# 3_waffling60-MX_mcu.net
KiCad netlist of a schematic drawn in Altium Designer
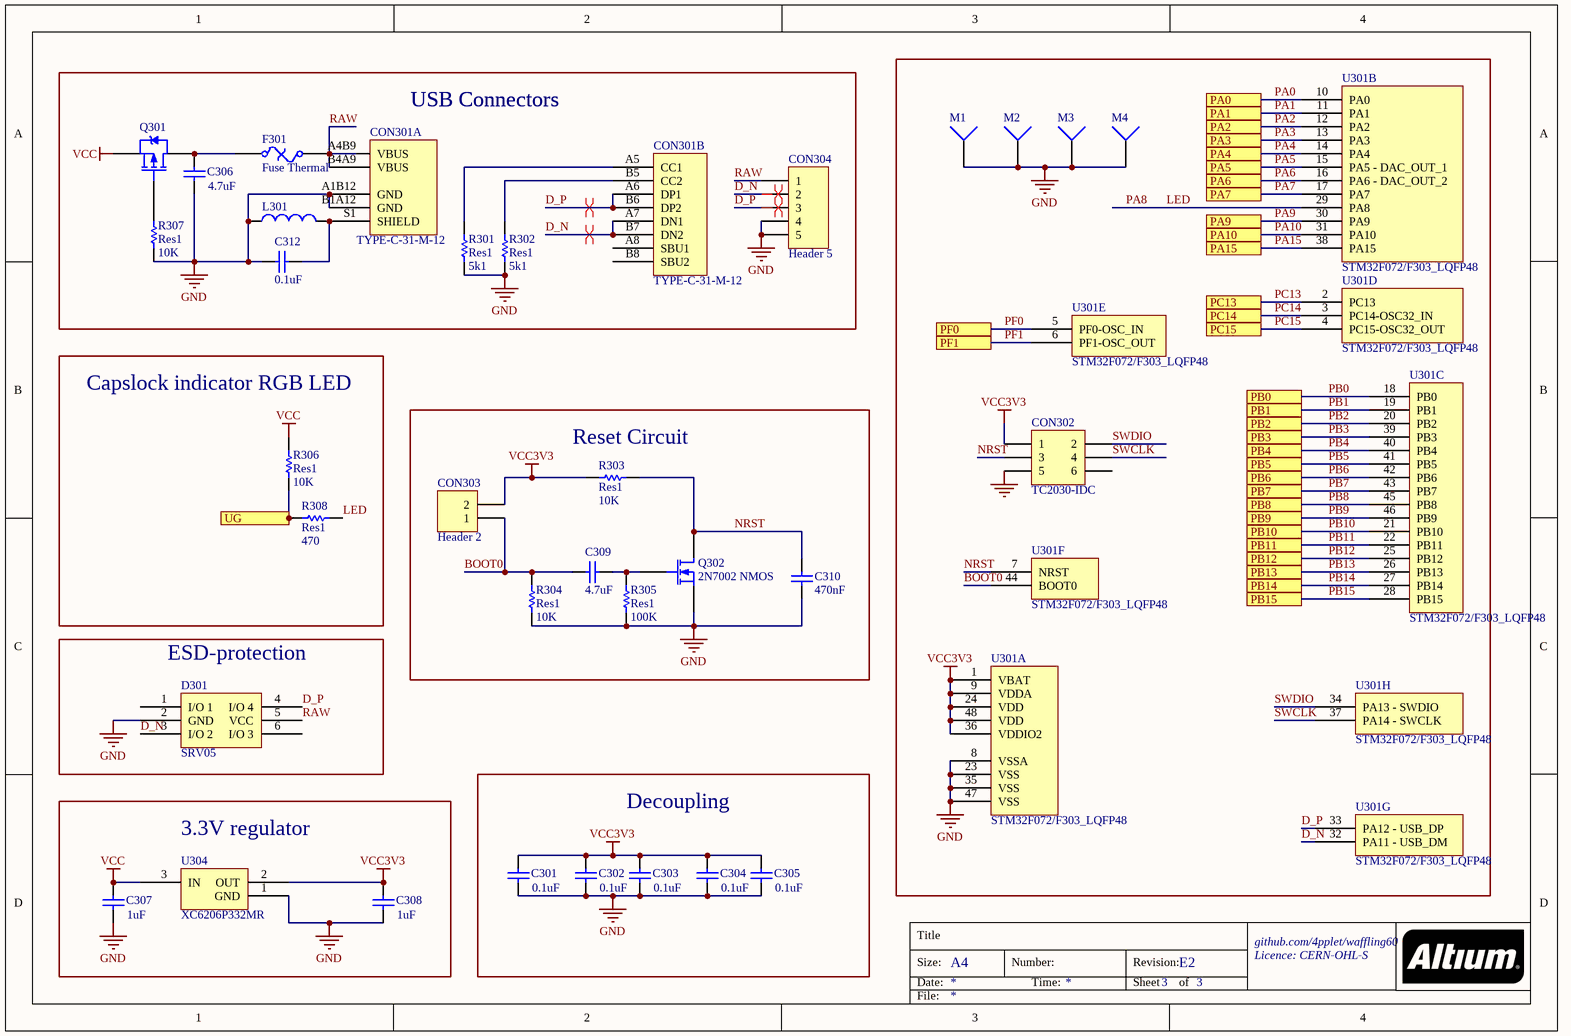
[diagram p0: 3_waffling60-MX_mcu.SchDoc]

(export (version "E")
  (design (tool "Eeschema 10.0.6"))
  (components
    (comp (ref "C301")
      (value "0.1uF")
      (footprint "C0603[1608]")
      (description "Capacitor")
      (fields (field (name "LCSC PART #") "C14663") (field (name "MRF.PART") "CC0603KRX7R9BB104"))
      (libsource (lib "Miscellaneous Devices") (part "Cap"))
    )
    (comp (ref "C302")
      (value "0.1uF")
      (footprint "C0603[1608]")
      (description "Capacitor")
      (fields (field (name "LCSC PART #") "C14663") (field (name "MRF.PART") "CC0603KRX7R9BB104"))
      (libsource (lib "Miscellaneous Devices") (part "Cap"))
    )
    (comp (ref "C303")
      (value "0.1uF")
      (footprint "C0603[1608]")
      (description "Capacitor")
      (fields (field (name "LCSC PART #") "C14663") (field (name "MRF.PART") "CC0603KRX7R9BB104"))
      (libsource (lib "Miscellaneous Devices") (part "Cap"))
    )
    (comp (ref "C304")
      (value "0.1uF")
      (footprint "C0603[1608]")
      (description "Capacitor")
      (fields (field (name "LCSC PART #") "C14663") (field (name "MRF.PART") "CC0603KRX7R9BB104"))
      (libsource (lib "Miscellaneous Devices") (part "Cap"))
    )
    (comp (ref "C305")
      (value "0.1uF")
      (footprint "C0603[1608]")
      (description "Capacitor")
      (fields (field (name "LCSC PART #") "C14663") (field (name "MRF.PART") "CC0603KRX7R9BB104"))
      (libsource (lib "Miscellaneous Devices") (part "Cap"))
    )
    (comp (ref "C306")
      (value "4.7uF")
      (footprint "C0603[1608]")
      (description "Capacitor")
      (fields (field (name "LCSC PART #") "C19666") (field (name "MRF.PART") "CL10A475KO8NNNC"))
      (libsource (lib "Miscellaneous Devices") (part "Cap"))
    )
    (comp (ref "C307")
      (value "1uF")
      (footprint "C0603[1608]")
      (description "Capacitor")
      (fields (field (name "LCSC PART #") "C15849") (field (name "MRF.PART") "CL10A105KB8NNNC"))
      (libsource (lib "Miscellaneous Devices") (part "Cap"))
    )
    (comp (ref "C308")
      (value "1uF")
      (footprint "C0603[1608]")
      (description "Capacitor")
      (fields (field (name "LCSC PART #") "C15849") (field (name "MRF.PART") "CL10A105KB8NNNC"))
      (libsource (lib "Miscellaneous Devices") (part "Cap"))
    )
    (comp (ref "C309")
      (value "4.7uF")
      (footprint "C0603[1608]")
      (description "Capacitor")
      (fields (field (name "LCSC PART #") "C19666") (field (name "MRF.PART") "CL10A475KO8NNNC"))
      (libsource (lib "Miscellaneous Devices") (part "Cap"))
    )
    (comp (ref "C310")
      (value "470nF")
      (footprint "C0603[1608]")
      (description "Capacitor")
      (fields (field (name "LCSC PART #") "C1623") (field (name "MRF.PART") "CL10B474KA8NNNC"))
      (libsource (lib "Miscellaneous Devices") (part "Cap"))
    )
    (comp (ref "C312")
      (value "0.1uF")
      (footprint "C0603[1608]")
      (description "Capacitor")
      (fields (field (name "LCSC PART #") "C14663") (field (name "MRF.PART") "CC0603KRX7R9BB104"))
      (libsource (lib "Miscellaneous Devices") (part "Cap"))
    )
    (comp (ref "CON301")
      (value "TYPE-C-31-M-12")
      (footprint "TYPE-C-31-M-12")
      (fields (field (name "LCSC PART #") "C165948"))
      (libsource (lib "Schlib1") (part "TYPE-C-31-M-12"))
    )
    (comp (ref "CON302")
      (value "TC2030-IDC")
      (footprint "TC2030-IDC-NL")
      (description "Header, 3-Pin, Dual row")
      (libsource (lib "Miscellaneous Connectors") (part "Header 3X2"))
    )
    (comp (ref "CON303")
      (value "Header 2")
      (footprint "HDR1X2")
      (description "Header, 2-Pin")
      (libsource (lib "Miscellaneous Connectors") (part "Header 2"))
    )
    (comp (ref "CON304")
      (value "Header 5")
      (footprint "UDB_COMBO_JST_MOLEX")
      (description "JST for USB daughter board")
      (fields (field (name "LCSC PART #") "C145956"))
      (libsource (lib "Miscellaneous Connectors") (part "Header 5"))
    )
    (comp (ref "D301")
      (value "SRV05")
      (footprint "SOT-23-6")
      (fields (field (name "LCSC PART #") "C85364") (field (name "MRF.PART") "SRV05-4-P-T7"))
      (libsource (lib "Keebs") (part "SRV05"))
    )
    (comp (ref "F301")
      (value "Fuse Thermal")
      (footprint "C1206[3216]")
      (description "Thermal Fuse")
      (fields (field (name "LCSC PART #") "C135338") (field (name "MRF.PART") "ASMD1206-050"))
      (libsource (lib "Miscellaneous Devices") (part "Fuse Thermal"))
    )
    (comp (ref "L301")
      (value "Inductor")
      (footprint "L0805")
      (fields (field (name "LCSC PART #") "C1015") (field (name "MRF.PART") "GZ2012D101TF"))
      (libsource (lib "Simulation Generic Components") (part "Inductor"))
    )
    (comp (ref "M1")
      (value "Socket")
      (footprint "mounting_hole")
      (libsource (lib "Miscellaneous Connectors") (part "Socket"))
    )
    (comp (ref "M2")
      (value "Socket")
      (footprint "mounting_hole")
      (libsource (lib "Miscellaneous Connectors") (part "Socket"))
    )
    (comp (ref "M3")
      (value "Socket")
      (footprint "mounting_hole")
      (libsource (lib "Miscellaneous Connectors") (part "Socket"))
    )
    (comp (ref "M4")
      (value "Socket")
      (footprint "mounting_hole")
      (libsource (lib "Miscellaneous Connectors") (part "Socket"))
    )
    (comp (ref "Q301")
      (value "PMOS-2")
      (footprint "SOT-23-3")
      (description "P-Channel Power MOSFET")
      (fields (field (name "LCSC PART #") "C10487") (field (name "MRF.PART") "SI2301CDS-T1-GE3"))
      (libsource (lib "Miscellaneous Devices") (part "PMOS-2"))
    )
    (comp (ref "Q302")
      (value "2N7002 NMOS")
      (footprint "SOT-23-3")
      (description "N-Channel MOSFET")
      (fields (field (name "LCSC PART #") "C8545") (field (name "MRF.PART") "2N7002"))
      (libsource (lib "Miscellaneous Devices") (part "MOSFET-N"))
    )
    (comp (ref "R301")
      (value "Res1")
      (footprint "R0603[1608]")
      (description "Resistor")
      (fields
        (field (name "ALTIUM_VALUE") "5k1")
        (field (name "LCSC PART #") "C23186")
        (field (name "MRF.PART") "0603WAF5101T5E")
      )
      (libsource (lib "Miscellaneous Devices") (part "Res1"))
    )
    (comp (ref "R302")
      (value "Res1")
      (footprint "R0603[1608]")
      (description "Resistor")
      (fields
        (field (name "ALTIUM_VALUE") "5k1")
        (field (name "LCSC PART #") "C23186")
        (field (name "MRF.PART") "0603WAF5101T5E")
      )
      (libsource (lib "Miscellaneous Devices") (part "Res1"))
    )
    (comp (ref "R303")
      (value "Res1")
      (footprint "R0603[1608]")
      (description "Resistor")
      (fields
        (field (name "ALTIUM_VALUE") "10K")
        (field (name "LCSC PART #") "C25804")
        (field (name "MRF.PART") "0603WAF1002T5E")
      )
      (libsource (lib "Miscellaneous Devices") (part "Res1"))
    )
    (comp (ref "R304")
      (value "Res1")
      (footprint "R0603[1608]")
      (description "Resistor")
      (fields
        (field (name "ALTIUM_VALUE") "10K")
        (field (name "LCSC PART #") "C25804")
        (field (name "MRF.PART") "0603WAF1002T5E")
      )
      (libsource (lib "Miscellaneous Devices") (part "Res1"))
    )
    (comp (ref "R305")
      (value "Res1")
      (footprint "R0603[1608]")
      (description "Resistor")
      (fields
        (field (name "ALTIUM_VALUE") "100K")
        (field (name "LCSC PART #") "C25803")
        (field (name "MRF.PART") "0603WAF1003T5E")
      )
      (libsource (lib "Miscellaneous Devices") (part "Res1"))
    )
    (comp (ref "R306")
      (value "Res1")
      (footprint "R0603[1608]")
      (description "Resistor")
      (fields
        (field (name "ALTIUM_VALUE") "10K")
        (field (name "LCSC PART #") "C25804")
        (field (name "MRF.PART") "0603WAF1002T5E")
      )
      (libsource (lib "Miscellaneous Devices") (part "Res1"))
    )
    (comp (ref "R307")
      (value "Res1")
      (footprint "R0603[1608]")
      (description "Resistor")
      (fields
        (field (name "ALTIUM_VALUE") "10K")
        (field (name "LCSC PART #") "C25804")
        (field (name "MRF.PART") "0603WAF1002T5E")
      )
      (libsource (lib "Miscellaneous Devices") (part "Res1"))
    )
    (comp (ref "R308")
      (value "Res1")
      (footprint "R0603[1608]")
      (description "Resistor")
      (fields
        (field (name "ALTIUM_VALUE") "470")
        (field (name "LCSC PART #") "C23179")
        (field (name "MRF.PART") "0603WAF4700T5E")
      )
      (libsource (lib "Miscellaneous Devices") (part "Res1"))
    )
    (comp (ref "U301")
      (value "STM32F072/F303_LQFP48")
      (footprint "STM32 - COMBO 7X7MM")
      (fields (field (name "LCSC PART #") "C915660") (field (name "MRF.PART") "APM32F072CBT6"))
      (libsource (lib "Keebs") (part "STM32F072/F303_LQFP48"))
    )
    (comp (ref "U304")
      (value "XC6206P332MR")
      (footprint "SOT-23-3")
      (fields (field (name "LCSC PART #") "C5446"))
      (libsource (lib "Keebs") (part "SOT23 LDO"))
    )
  )
  (nets
    (net (code "1") (name "/BOOT0") (class "Default")
      (node (ref "C309") (pin "1") (pinfunction "1_1") (pintype "passive"))
      (node (ref "CON303") (pin "1") (pinfunction "1_1") (pintype "passive"))
      (node (ref "R304") (pin "1") (pinfunction "1_1") (pintype "passive"))
      (node (ref "U301") (pin "44") (pinfunction "BOOT0_44") (pintype "passive"))
    )
    (net (code "2") (name "/D_N") (class "Default")
      (node (ref "CON301") (pin "A7") (pinfunction "DN1_A7") (pintype "passive"))
      (node (ref "CON301") (pin "B7") (pinfunction "DN2_B7") (pintype "passive"))
      (node (ref "CON304") (pin "2") (pinfunction "2_2") (pintype "passive"))
      (node (ref "D301") (pin "3") (pinfunction "I/O_2_3") (pintype "passive"))
      (node (ref "U301") (pin "32") (pinfunction "PA11_-_USB_DM_32") (pintype "passive"))
    )
    (net (code "3") (name "/D_P") (class "Default")
      (node (ref "CON301") (pin "A6") (pinfunction "DP1_A6") (pintype "passive"))
      (node (ref "CON301") (pin "B6") (pinfunction "DP2_B6") (pintype "passive"))
      (node (ref "CON304") (pin "3") (pinfunction "3_3") (pintype "passive"))
      (node (ref "D301") (pin "4") (pinfunction "I/O_4_4") (pintype "passive"))
      (node (ref "U301") (pin "33") (pinfunction "PA12_-_USB_DP_33") (pintype "passive"))
    )
    (net (code "4") (name "/LED") (class "Default")
      (node (ref "R308") (pin "2") (pinfunction "2_2") (pintype "passive"))
      (node (ref "U301") (pin "29") (pinfunction "PA8_29") (pintype "passive"))
    )
    (net (code "5") (name "/NRST") (class "Default")
      (node (ref "C310") (pin "1") (pinfunction "1_1") (pintype "passive"))
      (node (ref "CON302") (pin "3") (pinfunction "3_3") (pintype "passive"))
      (node (ref "Q302") (pin "3") (pinfunction "D_3") (pintype "passive"))
      (node (ref "R303") (pin "2") (pinfunction "2_2") (pintype "passive"))
      (node (ref "U301") (pin "7") (pinfunction "NRST_7") (pintype "passive"))
    )
    (net (code "6") (name "/PA0") (class "Default")
      (node (ref "U301") (pin "10") (pinfunction "PA0_10") (pintype "passive"))
    )
    (net (code "7") (name "/PA1") (class "Default")
      (node (ref "U301") (pin "11") (pinfunction "PA1_11") (pintype "passive"))
    )
    (net (code "8") (name "/PA2") (class "Default")
      (node (ref "U301") (pin "12") (pinfunction "PA2_12") (pintype "passive"))
    )
    (net (code "9") (name "/PA3") (class "Default")
      (node (ref "U301") (pin "13") (pinfunction "PA3_13") (pintype "passive"))
    )
    (net (code "10") (name "/PA4") (class "Default")
      (node (ref "U301") (pin "14") (pinfunction "PA4_14") (pintype "passive"))
    )
    (net (code "11") (name "/PA5") (class "Default")
      (node (ref "U301") (pin "15") (pinfunction "PA5_-_DAC_OUT_1_15") (pintype "passive"))
    )
    (net (code "12") (name "/PA6") (class "Default")
      (node (ref "U301") (pin "16") (pinfunction "PA6_-_DAC_OUT_2_16") (pintype "passive"))
    )
    (net (code "13") (name "/PA7") (class "Default")
      (node (ref "U301") (pin "17") (pinfunction "PA7_17") (pintype "passive"))
    )
    (net (code "14") (name "/PA9") (class "Default")
      (node (ref "U301") (pin "30") (pinfunction "PA9_30") (pintype "passive"))
    )
    (net (code "15") (name "/PA10") (class "Default")
      (node (ref "U301") (pin "31") (pinfunction "PA10_31") (pintype "passive"))
    )
    (net (code "16") (name "/PA15") (class "Default")
      (node (ref "U301") (pin "38") (pinfunction "PA15_38") (pintype "passive"))
    )
    (net (code "17") (name "/PB0") (class "Default")
      (node (ref "U301") (pin "18") (pinfunction "PB0_18") (pintype "passive"))
    )
    (net (code "18") (name "/PB1") (class "Default")
      (node (ref "U301") (pin "19") (pinfunction "PB1_19") (pintype "passive"))
    )
    (net (code "19") (name "/PB2") (class "Default")
      (node (ref "U301") (pin "20") (pinfunction "PB2_20") (pintype "passive"))
    )
    (net (code "20") (name "/PB3") (class "Default")
      (node (ref "U301") (pin "39") (pinfunction "PB3_39") (pintype "passive"))
    )
    (net (code "21") (name "/PB4") (class "Default")
      (node (ref "U301") (pin "40") (pinfunction "PB4_40") (pintype "passive"))
    )
    (net (code "22") (name "/PB5") (class "Default")
      (node (ref "U301") (pin "41") (pinfunction "PB5_41") (pintype "passive"))
    )
    (net (code "23") (name "/PB6") (class "Default")
      (node (ref "U301") (pin "42") (pinfunction "PB6_42") (pintype "passive"))
    )
    (net (code "24") (name "/PB7") (class "Default")
      (node (ref "U301") (pin "43") (pinfunction "PB7_43") (pintype "passive"))
    )
    (net (code "25") (name "/PB8") (class "Default")
      (node (ref "U301") (pin "45") (pinfunction "PB8_45") (pintype "passive"))
    )
    (net (code "26") (name "/PB9") (class "Default")
      (node (ref "U301") (pin "46") (pinfunction "PB9_46") (pintype "passive"))
    )
    (net (code "27") (name "/PB10") (class "Default")
      (node (ref "U301") (pin "21") (pinfunction "PB10_21") (pintype "passive"))
    )
    (net (code "28") (name "/PB11") (class "Default")
      (node (ref "U301") (pin "22") (pinfunction "PB11_22") (pintype "passive"))
    )
    (net (code "29") (name "/PB12") (class "Default")
      (node (ref "U301") (pin "25") (pinfunction "PB12_25") (pintype "passive"))
    )
    (net (code "30") (name "/PB13") (class "Default")
      (node (ref "U301") (pin "26") (pinfunction "PB13_26") (pintype "passive"))
    )
    (net (code "31") (name "/PB14") (class "Default")
      (node (ref "U301") (pin "27") (pinfunction "PB14_27") (pintype "passive"))
    )
    (net (code "32") (name "/PB15") (class "Default")
      (node (ref "U301") (pin "28") (pinfunction "PB15_28") (pintype "passive"))
    )
    (net (code "33") (name "/PC13") (class "Default")
      (node (ref "U301") (pin "2") (pinfunction "PC13_2") (pintype "passive"))
    )
    (net (code "34") (name "/PC14") (class "Default")
      (node (ref "U301") (pin "3") (pinfunction "PC14-OSC32_IN_3") (pintype "passive"))
    )
    (net (code "35") (name "/PC15") (class "Default")
      (node (ref "U301") (pin "4") (pinfunction "PC15-OSC32_OUT_4") (pintype "passive"))
    )
    (net (code "36") (name "/PF0") (class "Default")
      (node (ref "U301") (pin "5") (pinfunction "PF0-OSC_IN_5") (pintype "passive"))
    )
    (net (code "37") (name "/PF1") (class "Default")
      (node (ref "U301") (pin "6") (pinfunction "PF1-OSC_OUT_6") (pintype "passive"))
    )
    (net (code "38") (name "/RAW") (class "Default")
      (node (ref "CON301") (pin "A4B9") (pinfunction "VBUS_A4B9") (pintype "passive"))
      (node (ref "CON301") (pin "B4A9") (pinfunction "VBUS_B4A9") (pintype "passive"))
      (node (ref "CON304") (pin "1") (pinfunction "1_1") (pintype "passive"))
      (node (ref "D301") (pin "5") (pinfunction "VCC_5") (pintype "passive"))
      (node (ref "F301") (pin "2") (pinfunction "2_2") (pintype "passive"))
    )
    (net (code "39") (name "/SWCLK") (class "Default")
      (node (ref "CON302") (pin "4") (pinfunction "4_4") (pintype "passive"))
      (node (ref "U301") (pin "37") (pinfunction "PA14_-_SWCLK_37") (pintype "passive"))
    )
    (net (code "40") (name "/SWDIO") (class "Default")
      (node (ref "CON302") (pin "2") (pinfunction "2_2") (pintype "passive"))
      (node (ref "U301") (pin "34") (pinfunction "PA13_-_SWDIO_34") (pintype "passive"))
    )
    (net (code "41") (name "/UG") (class "Default")
      (node (ref "R306") (pin "2") (pinfunction "2_2") (pintype "passive"))
      (node (ref "R308") (pin "1") (pinfunction "1_1") (pintype "passive"))
    )
    (net (code "42") (name "GND") (class "Default")
      (node (ref "C301") (pin "1") (pinfunction "1_1") (pintype "passive"))
      (node (ref "C302") (pin "1") (pinfunction "1_1") (pintype "passive"))
      (node (ref "C303") (pin "1") (pinfunction "1_1") (pintype "passive"))
      (node (ref "C304") (pin "1") (pinfunction "1_1") (pintype "passive"))
      (node (ref "C305") (pin "1") (pinfunction "1_1") (pintype "passive"))
      (node (ref "C306") (pin "1") (pinfunction "1_1") (pintype "passive"))
      (node (ref "C307") (pin "1") (pinfunction "1_1") (pintype "passive"))
      (node (ref "C308") (pin "1") (pinfunction "1_1") (pintype "passive"))
      (node (ref "C310") (pin "2") (pinfunction "2_2") (pintype "passive"))
      (node (ref "C312") (pin "1") (pinfunction "1_1") (pintype "passive"))
      (node (ref "CON301") (pin "A1B12") (pinfunction "GND_A1B12") (pintype "passive"))
      (node (ref "CON301") (pin "B1A12") (pinfunction "GND_B1A12") (pintype "passive"))
      (node (ref "CON302") (pin "5") (pinfunction "5_5") (pintype "passive"))
      (node (ref "CON304") (pin "4") (pinfunction "4_4") (pintype "passive"))
      (node (ref "CON304") (pin "5") (pinfunction "5_5") (pintype "passive"))
      (node (ref "D301") (pin "2") (pinfunction "GND_2") (pintype "passive"))
      (node (ref "L301") (pin "1") (pinfunction "1_1") (pintype "passive"))
      (node (ref "M1") (pin "1") (pinfunction "1_1") (pintype "passive"))
      (node (ref "M2") (pin "1") (pinfunction "1_1") (pintype "passive"))
      (node (ref "M3") (pin "1") (pinfunction "1_1") (pintype "passive"))
      (node (ref "M4") (pin "1") (pinfunction "1_1") (pintype "passive"))
      (node (ref "Q302") (pin "2") (pinfunction "S_2") (pintype "passive"))
      (node (ref "R301") (pin "2") (pinfunction "2_2") (pintype "passive"))
      (node (ref "R302") (pin "2") (pinfunction "2_2") (pintype "passive"))
      (node (ref "R304") (pin "2") (pinfunction "2_2") (pintype "passive"))
      (node (ref "R305") (pin "2") (pinfunction "2_2") (pintype "passive"))
      (node (ref "R307") (pin "2") (pinfunction "2_2") (pintype "passive"))
      (node (ref "U301") (pin "23") (pinfunction "VSS_23") (pintype "passive"))
      (node (ref "U301") (pin "35") (pinfunction "VSS_35") (pintype "passive"))
      (node (ref "U301") (pin "47") (pinfunction "VSS_47") (pintype "passive"))
      (node (ref "U301") (pin "8") (pinfunction "VSSA_8") (pintype "passive"))
      (node (ref "U304") (pin "1") (pinfunction "GND_1") (pintype "passive"))
    )
    (net (code "43") (name "Net-(CON301A-SHIELD)") (class "Default")
      (node (ref "C312") (pin "2") (pinfunction "2_2") (pintype "passive"))
      (node (ref "CON301") (pin "S1") (pinfunction "SHIELD_S1") (pintype "passive"))
      (node (ref "L301") (pin "2") (pinfunction "2_2") (pintype "passive"))
    )
    (net (code "44") (name "Net-(CON301B-CC1)") (class "Default")
      (node (ref "CON301") (pin "A5") (pinfunction "CC1_A5") (pintype "passive"))
      (node (ref "R301") (pin "1") (pinfunction "1_1") (pintype "passive"))
    )
    (net (code "45") (name "Net-(CON301B-CC2)") (class "Default")
      (node (ref "CON301") (pin "B5") (pinfunction "CC2_B5") (pintype "passive"))
      (node (ref "R302") (pin "1") (pinfunction "1_1") (pintype "passive"))
    )
    (net (code "46") (name "Net-(Q301-D)") (class "Default")
      (node (ref "C306") (pin "2") (pinfunction "2_2") (pintype "passive"))
      (node (ref "F301") (pin "1") (pinfunction "1_1") (pintype "passive"))
      (node (ref "Q301") (pin "3") (pinfunction "D_3") (pintype "passive"))
    )
    (net (code "47") (name "Net-(Q301-G)") (class "Default")
      (node (ref "Q301") (pin "1") (pinfunction "G_1") (pintype "passive"))
      (node (ref "R307") (pin "1") (pinfunction "1_1") (pintype "passive"))
    )
    (net (code "48") (name "Net-(Q302-G)") (class "Default")
      (node (ref "C309") (pin "2") (pinfunction "2_2") (pintype "passive"))
      (node (ref "Q302") (pin "1") (pinfunction "G_1") (pintype "passive"))
      (node (ref "R305") (pin "1") (pinfunction "1_1") (pintype "passive"))
    )
    (net (code "49") (name "VCC") (class "Default")
      (node (ref "C307") (pin "2") (pinfunction "2_2") (pintype "passive"))
      (node (ref "Q301") (pin "2") (pinfunction "S_2") (pintype "passive"))
      (node (ref "R306") (pin "1") (pinfunction "1_1") (pintype "passive"))
      (node (ref "U304") (pin "3") (pinfunction "IN_3") (pintype "passive"))
    )
    (net (code "50") (name "VCC3V3") (class "Default")
      (node (ref "C301") (pin "2") (pinfunction "2_2") (pintype "passive"))
      (node (ref "C302") (pin "2") (pinfunction "2_2") (pintype "passive"))
      (node (ref "C303") (pin "2") (pinfunction "2_2") (pintype "passive"))
      (node (ref "C304") (pin "2") (pinfunction "2_2") (pintype "passive"))
      (node (ref "C305") (pin "2") (pinfunction "2_2") (pintype "passive"))
      (node (ref "C308") (pin "2") (pinfunction "2_2") (pintype "passive"))
      (node (ref "CON302") (pin "1") (pinfunction "1_1") (pintype "passive"))
      (node (ref "CON303") (pin "2") (pinfunction "2_2") (pintype "passive"))
      (node (ref "R303") (pin "1") (pinfunction "1_1") (pintype "passive"))
      (node (ref "U301") (pin "1") (pinfunction "VBAT_1") (pintype "passive"))
      (node (ref "U301") (pin "24") (pinfunction "VDD_24") (pintype "passive"))
      (node (ref "U301") (pin "36") (pinfunction "VDDIO2_36") (pintype "passive"))
      (node (ref "U301") (pin "48") (pinfunction "VDD_48") (pintype "passive"))
      (node (ref "U301") (pin "9") (pinfunction "VDDA_9") (pintype "passive"))
      (node (ref "U304") (pin "2") (pinfunction "OUT_2") (pintype "passive"))
    )
    (net (code "51") (name "unconnected-(CON301B-SBU1-PadA8)") (class "Default")
      (node (ref "CON301") (pin "A8") (pinfunction "SBU1_A8") (pintype "passive"))
    )
    (net (code "52") (name "unconnected-(CON301B-SBU2-PadB8)") (class "Default")
      (node (ref "CON301") (pin "B8") (pinfunction "SBU2_B8") (pintype "passive"))
    )
    (net (code "53") (name "unconnected-(CON302-Pad6)") (class "Default")
      (node (ref "CON302") (pin "6") (pinfunction "6_6") (pintype "passive"))
    )
    (net (code "54") (name "unconnected-(D301-I{slash}O_1-Pad1)") (class "Default")
      (node (ref "D301") (pin "1") (pinfunction "I/O_1_1") (pintype "passive"))
    )
    (net (code "55") (name "unconnected-(D301-I{slash}O_3-Pad6)") (class "Default")
      (node (ref "D301") (pin "6") (pinfunction "I/O_3_6") (pintype "passive"))
    )
  )
)
